# PCB_3U_DDS.net
KiCad netlist of a schematic drawn in Altium Designer
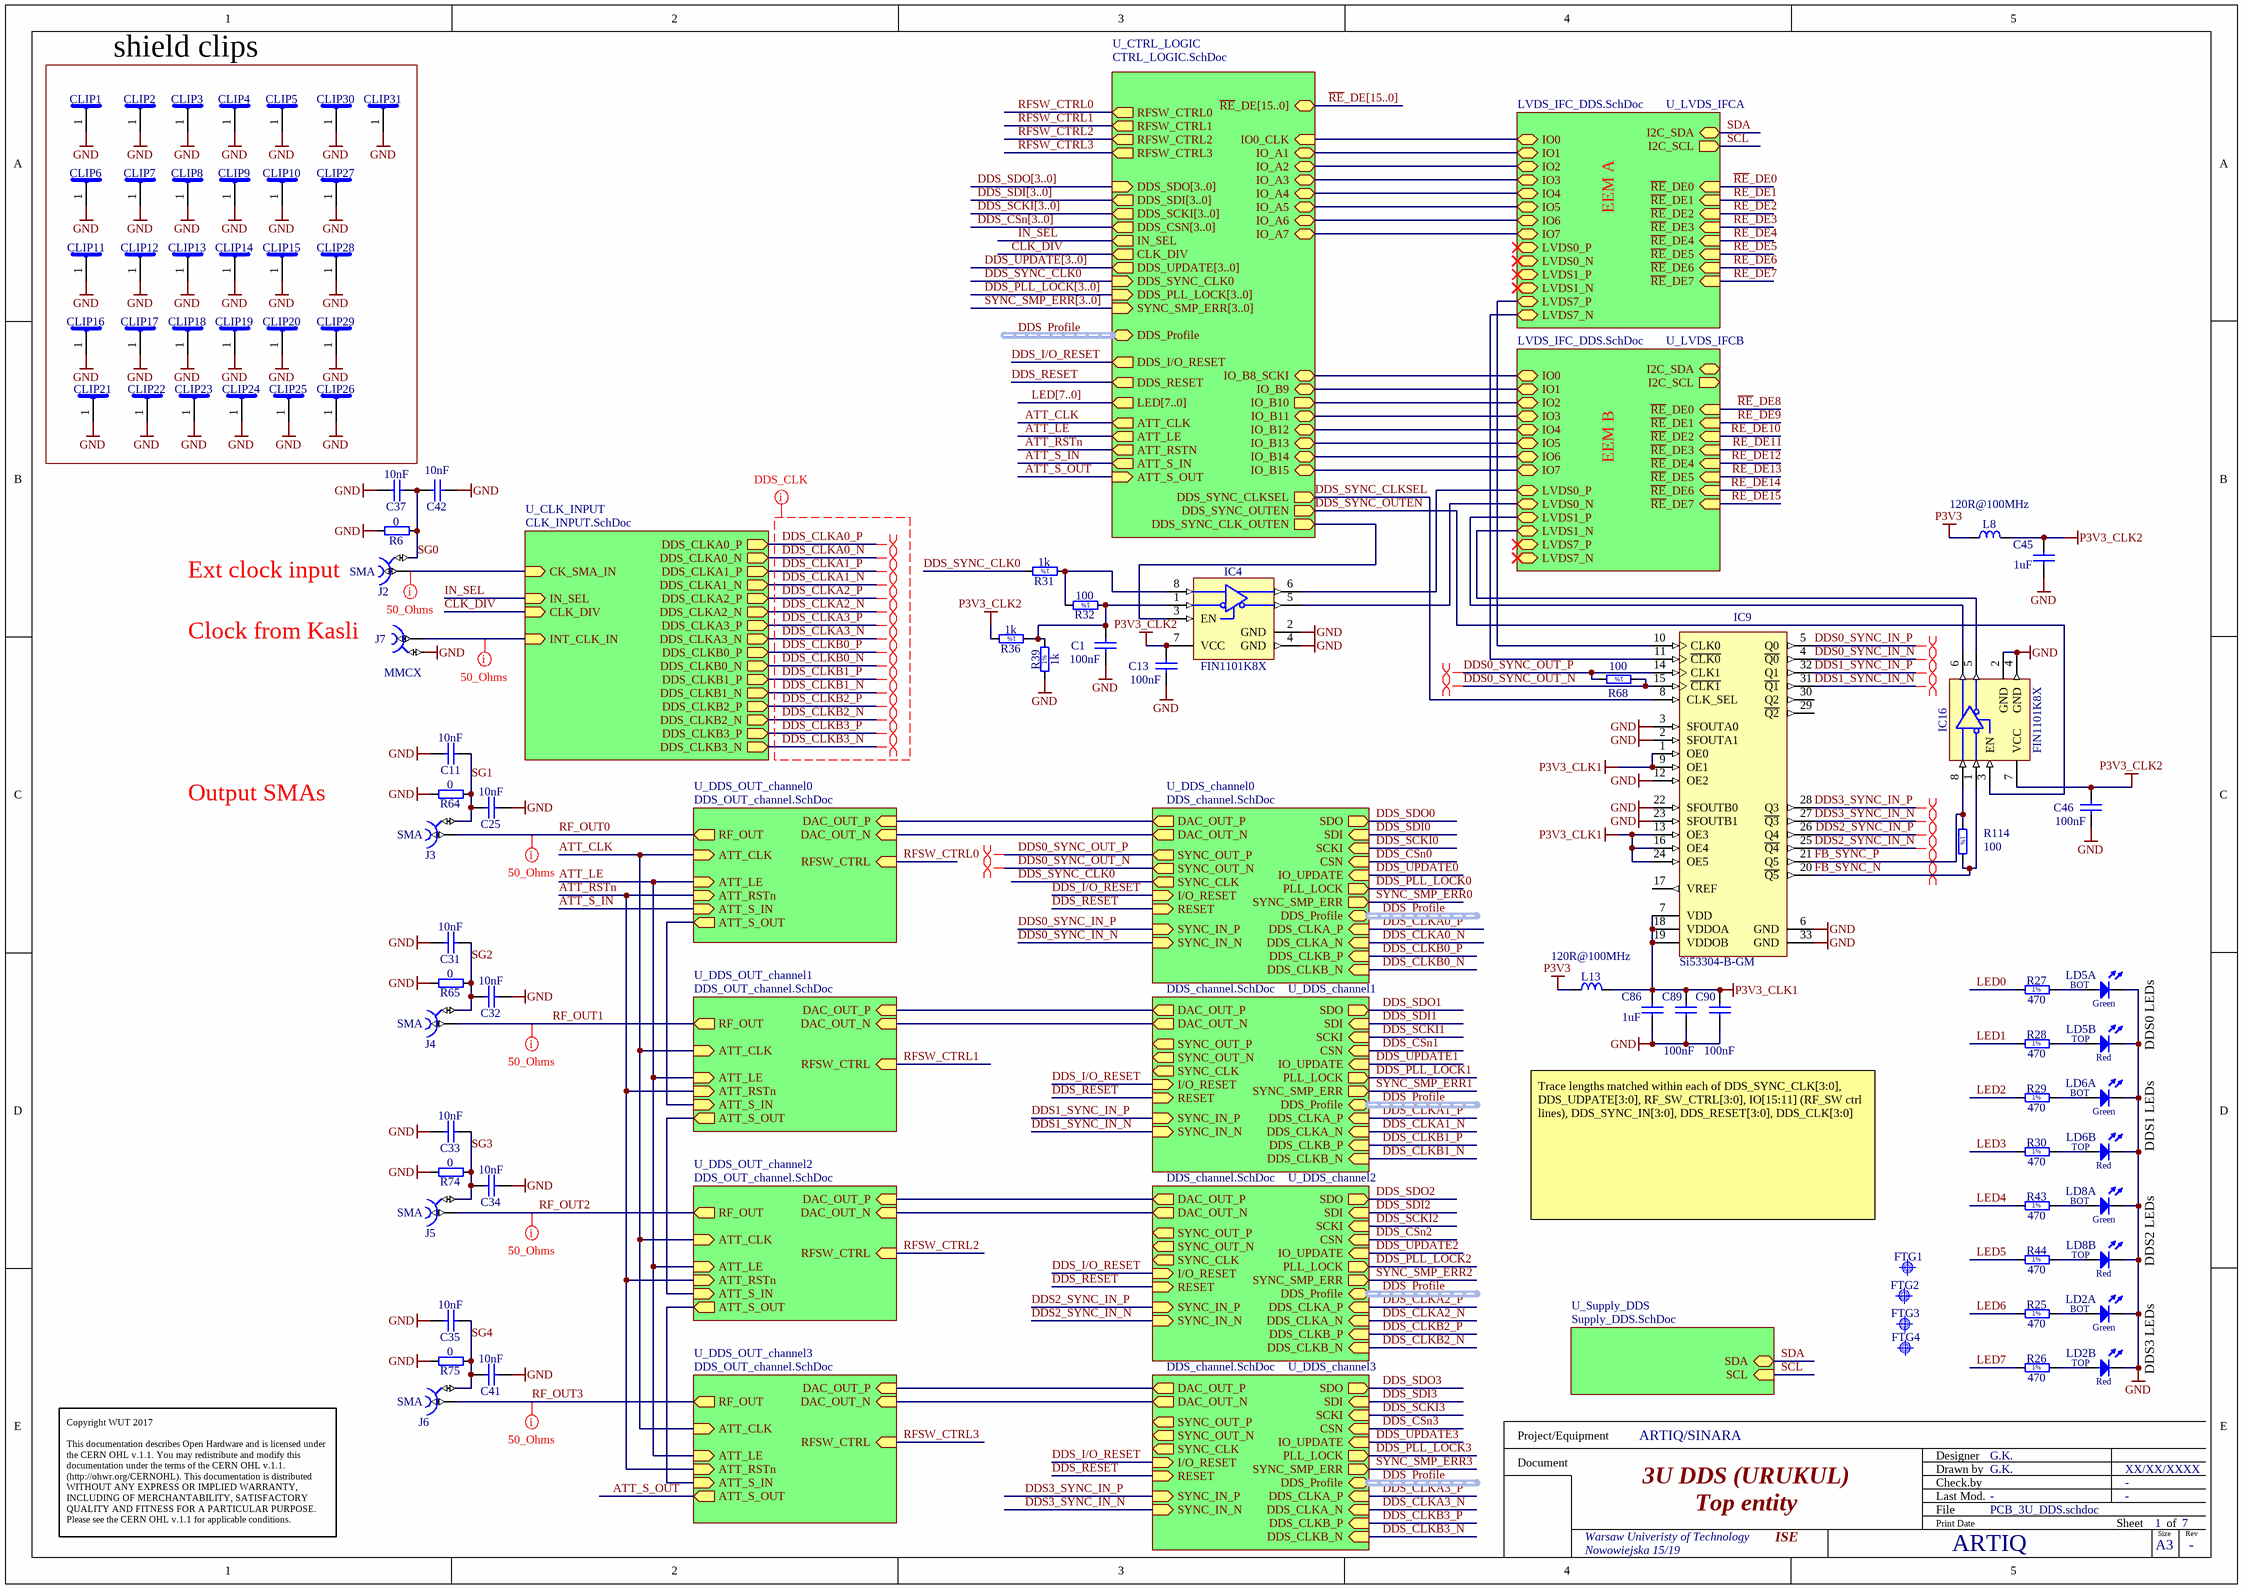
[diagram p0: PCB_3U_DDS.schdoc]

(export (version "E")
  (design (tool "Eeschema 10.0.6"))
  (components
    (comp (ref "C1")
      (value "100nF")
      (footprint "CAPC1005X55N")
      (description "Non-polarised capacitor")
      (fields
        (field (name "PART NUMBER") "CC0402_100NF_16V_10%_X5R")
        (field (name "VOLTAGE") "16V")
        (field (name "AUTHOR") "CERN DEM JLC")
      )
      (libsource (lib "Capacitors") (part "Capacitor - non polarized"))
    )
    (comp (ref "C11")
      (value "10nF")
      (footprint "CAPC1005X55N")
      (description "Non-polarised capacitor")
      (fields
        (field (name "PART NUMBER") "CC0402_10NF_16V_10%_X7R")
        (field (name "VOLTAGE") "16V")
        (field (name "AUTHOR") "CERN DEM JLC")
      )
      (libsource (lib "Capacitors") (part "Capacitor - non polarized"))
    )
    (comp (ref "C13")
      (value "100nF")
      (footprint "CAPC1005X55N")
      (description "Non-polarised capacitor")
      (fields
        (field (name "PART NUMBER") "CC0402_100NF_16V_10%_X5R")
        (field (name "VOLTAGE") "16V")
        (field (name "AUTHOR") "CERN DEM JLC")
      )
      (libsource (lib "Capacitors") (part "Capacitor - non polarized"))
    )
    (comp (ref "C25")
      (value "10nF")
      (footprint "CAPC1005X55N")
      (description "Non-polarised capacitor")
      (fields
        (field (name "PART NUMBER") "CC0402_10NF_16V_10%_X7R")
        (field (name "VOLTAGE") "16V")
        (field (name "AUTHOR") "CERN DEM JLC")
      )
      (libsource (lib "Capacitors") (part "Capacitor - non polarized"))
    )
    (comp (ref "C31")
      (value "10nF")
      (footprint "CAPC1005X55N")
      (description "Non-polarised capacitor")
      (fields
        (field (name "PART NUMBER") "CC0402_10NF_16V_10%_X7R")
        (field (name "VOLTAGE") "16V")
        (field (name "AUTHOR") "CERN DEM JLC")
      )
      (libsource (lib "Capacitors") (part "Capacitor - non polarized"))
    )
    (comp (ref "C32")
      (value "10nF")
      (footprint "CAPC1005X55N")
      (description "Non-polarised capacitor")
      (fields
        (field (name "PART NUMBER") "CC0402_10NF_16V_10%_X7R")
        (field (name "VOLTAGE") "16V")
        (field (name "AUTHOR") "CERN DEM JLC")
      )
      (libsource (lib "Capacitors") (part "Capacitor - non polarized"))
    )
    (comp (ref "C33")
      (value "10nF")
      (footprint "CAPC1005X55N")
      (description "Non-polarised capacitor")
      (fields
        (field (name "PART NUMBER") "CC0402_10NF_16V_10%_X7R")
        (field (name "VOLTAGE") "16V")
        (field (name "AUTHOR") "CERN DEM JLC")
      )
      (libsource (lib "Capacitors") (part "Capacitor - non polarized"))
    )
    (comp (ref "C34")
      (value "10nF")
      (footprint "CAPC1005X55N")
      (description "Non-polarised capacitor")
      (fields
        (field (name "PART NUMBER") "CC0402_10NF_16V_10%_X7R")
        (field (name "VOLTAGE") "16V")
        (field (name "AUTHOR") "CERN DEM JLC")
      )
      (libsource (lib "Capacitors") (part "Capacitor - non polarized"))
    )
    (comp (ref "C35")
      (value "10nF")
      (footprint "CAPC1005X55N")
      (description "Non-polarised capacitor")
      (fields
        (field (name "PART NUMBER") "CC0402_10NF_16V_10%_X7R")
        (field (name "VOLTAGE") "16V")
        (field (name "AUTHOR") "CERN DEM JLC")
      )
      (libsource (lib "Capacitors") (part "Capacitor - non polarized"))
    )
    (comp (ref "C37")
      (value "10nF")
      (footprint "CAPC1005X55N")
      (description "Non-polarised capacitor")
      (fields
        (field (name "PART NUMBER") "CC0402_10NF_16V_10%_X7R")
        (field (name "VOLTAGE") "16V")
        (field (name "AUTHOR") "CERN DEM JLC")
      )
      (libsource (lib "Capacitors") (part "Capacitor - non polarized"))
    )
    (comp (ref "C41")
      (value "10nF")
      (footprint "CAPC1005X55N")
      (description "Non-polarised capacitor")
      (fields
        (field (name "PART NUMBER") "CC0402_10NF_16V_10%_X7R")
        (field (name "VOLTAGE") "16V")
        (field (name "AUTHOR") "CERN DEM JLC")
      )
      (libsource (lib "Capacitors") (part "Capacitor - non polarized"))
    )
    (comp (ref "C42")
      (value "10nF")
      (footprint "CAPC1005X55N")
      (description "Non-polarised capacitor")
      (fields
        (field (name "PART NUMBER") "CC0402_10NF_16V_10%_X7R")
        (field (name "VOLTAGE") "16V")
        (field (name "AUTHOR") "CERN DEM JLC")
      )
      (libsource (lib "Capacitors") (part "Capacitor - non polarized"))
    )
    (comp (ref "C45")
      (value "1uF")
      (footprint "CAPC1005X55N")
      (description "Non-polarised capacitor")
      (fields
        (field (name "PART NUMBER") "CC0402_1UF_16V_10%_X5R")
        (field (name "VOLTAGE") "16V")
        (field (name "AUTHOR") "CERN DEM JLC")
      )
      (libsource (lib "Capacitors") (part "Capacitor - non polarized"))
    )
    (comp (ref "C46")
      (value "100nF")
      (footprint "CAPC1005X55N")
      (description "Non-polarised capacitor")
      (fields
        (field (name "PART NUMBER") "CC0402_100NF_16V_10%_X5R")
        (field (name "VOLTAGE") "16V")
        (field (name "AUTHOR") "CERN DEM JLC")
      )
      (libsource (lib "Capacitors") (part "Capacitor - non polarized"))
    )
    (comp (ref "C86")
      (value "1uF")
      (footprint "CAPC1005X55N")
      (description "Non-polarised capacitor")
      (fields
        (field (name "PART NUMBER") "CC0402_1UF_16V_10%_X5R")
        (field (name "VOLTAGE") "16V")
        (field (name "AUTHOR") "CERN DEM JLC")
      )
      (libsource (lib "Capacitors") (part "Capacitor - non polarized"))
    )
    (comp (ref "C89")
      (value "100nF")
      (footprint "CAPC1005X55N")
      (description "Non-polarised capacitor")
      (fields
        (field (name "PART NUMBER") "CC0402_100NF_16V_10%_X5R")
        (field (name "VOLTAGE") "16V")
        (field (name "AUTHOR") "CERN DEM JLC")
      )
      (libsource (lib "Capacitors") (part "Capacitor - non polarized"))
    )
    (comp (ref "C90")
      (value "100nF")
      (footprint "CAPC1005X55N")
      (description "Non-polarised capacitor")
      (fields
        (field (name "PART NUMBER") "CC0402_100NF_16V_10%_X5R")
        (field (name "VOLTAGE") "16V")
        (field (name "AUTHOR") "CERN DEM JLC")
      )
      (libsource (lib "Capacitors") (part "Capacitor - non polarized"))
    )
    (comp (ref "CLIP1")
      (value "S1411-46R")
      (footprint "CLIP_HOLLAND-SHIELDING_LC")
      (description "Surface Mount Clip for PCB Screening Covers")
      (fields (field (name "MANUFACTURER") "HARWIN") (field (name "AUTHOR") "CERN DEM JLC"))
      (libsource (lib "LIBRARY_SCH") (part "SHIELD_CLIP"))
    )
    (comp (ref "CLIP2")
      (value "S1411-46R")
      (footprint "CLIP_HOLLAND-SHIELDING_LC")
      (description "Surface Mount Clip for PCB Screening Covers")
      (fields (field (name "MANUFACTURER") "HARWIN") (field (name "AUTHOR") "CERN DEM JLC"))
      (libsource (lib "LIBRARY_SCH") (part "SHIELD_CLIP"))
    )
    (comp (ref "CLIP3")
      (value "S1411-46R")
      (footprint "CLIP_HOLLAND-SHIELDING_LC")
      (description "Surface Mount Clip for PCB Screening Covers")
      (fields (field (name "MANUFACTURER") "HARWIN") (field (name "AUTHOR") "CERN DEM JLC"))
      (libsource (lib "LIBRARY_SCH") (part "SHIELD_CLIP"))
    )
    (comp (ref "CLIP4")
      (value "S1411-46R")
      (footprint "CLIP_HOLLAND-SHIELDING_LC")
      (description "Surface Mount Clip for PCB Screening Covers")
      (fields (field (name "MANUFACTURER") "HARWIN") (field (name "AUTHOR") "CERN DEM JLC"))
      (libsource (lib "LIBRARY_SCH") (part "SHIELD_CLIP"))
    )
    (comp (ref "CLIP5")
      (value "S1411-46R")
      (footprint "CLIP_HOLLAND-SHIELDING_LC")
      (description "Surface Mount Clip for PCB Screening Covers")
      (fields (field (name "MANUFACTURER") "HARWIN") (field (name "AUTHOR") "CERN DEM JLC"))
      (libsource (lib "LIBRARY_SCH") (part "SHIELD_CLIP"))
    )
    (comp (ref "CLIP6")
      (value "S1411-46R")
      (footprint "CLIP_HOLLAND-SHIELDING_LC")
      (description "Surface Mount Clip for PCB Screening Covers")
      (fields (field (name "MANUFACTURER") "HARWIN") (field (name "AUTHOR") "CERN DEM JLC"))
      (libsource (lib "LIBRARY_SCH") (part "SHIELD_CLIP"))
    )
    (comp (ref "CLIP7")
      (value "S1411-46R")
      (footprint "CLIP_HOLLAND-SHIELDING_LC")
      (description "Surface Mount Clip for PCB Screening Covers")
      (fields (field (name "MANUFACTURER") "HARWIN") (field (name "AUTHOR") "CERN DEM JLC"))
      (libsource (lib "LIBRARY_SCH") (part "SHIELD_CLIP"))
    )
    (comp (ref "CLIP8")
      (value "S1411-46R")
      (footprint "CLIP_HOLLAND-SHIELDING_LC")
      (description "Surface Mount Clip for PCB Screening Covers")
      (fields (field (name "MANUFACTURER") "HARWIN") (field (name "AUTHOR") "CERN DEM JLC"))
      (libsource (lib "LIBRARY_SCH") (part "SHIELD_CLIP"))
    )
    (comp (ref "CLIP9")
      (value "S1411-46R")
      (footprint "CLIP_HOLLAND-SHIELDING_LC")
      (description "Surface Mount Clip for PCB Screening Covers")
      (fields (field (name "MANUFACTURER") "HARWIN") (field (name "AUTHOR") "CERN DEM JLC"))
      (libsource (lib "LIBRARY_SCH") (part "SHIELD_CLIP"))
    )
    (comp (ref "CLIP10")
      (value "S1411-46R")
      (footprint "CLIP_HOLLAND-SHIELDING_LC")
      (description "Surface Mount Clip for PCB Screening Covers")
      (fields (field (name "MANUFACTURER") "HARWIN") (field (name "AUTHOR") "CERN DEM JLC"))
      (libsource (lib "LIBRARY_SCH") (part "SHIELD_CLIP"))
    )
    (comp (ref "CLIP11")
      (value "S1411-46R")
      (footprint "CLIP_HOLLAND-SHIELDING_LC")
      (description "Surface Mount Clip for PCB Screening Covers")
      (fields (field (name "MANUFACTURER") "HARWIN") (field (name "AUTHOR") "CERN DEM JLC"))
      (libsource (lib "LIBRARY_SCH") (part "SHIELD_CLIP"))
    )
    (comp (ref "CLIP12")
      (value "S1411-46R")
      (footprint "CLIP_HOLLAND-SHIELDING_LC")
      (description "Surface Mount Clip for PCB Screening Covers")
      (fields (field (name "MANUFACTURER") "HARWIN") (field (name "AUTHOR") "CERN DEM JLC"))
      (libsource (lib "LIBRARY_SCH") (part "SHIELD_CLIP"))
    )
    (comp (ref "CLIP13")
      (value "S1411-46R")
      (footprint "CLIP_HOLLAND-SHIELDING_LC")
      (description "Surface Mount Clip for PCB Screening Covers")
      (fields (field (name "MANUFACTURER") "HARWIN") (field (name "AUTHOR") "CERN DEM JLC"))
      (libsource (lib "LIBRARY_SCH") (part "SHIELD_CLIP"))
    )
    (comp (ref "CLIP14")
      (value "S1411-46R")
      (footprint "CLIP_HOLLAND-SHIELDING_LC")
      (description "Surface Mount Clip for PCB Screening Covers")
      (fields (field (name "MANUFACTURER") "HARWIN") (field (name "AUTHOR") "CERN DEM JLC"))
      (libsource (lib "LIBRARY_SCH") (part "SHIELD_CLIP"))
    )
    (comp (ref "CLIP15")
      (value "S1411-46R")
      (footprint "CLIP_HOLLAND-SHIELDING_LC")
      (description "Surface Mount Clip for PCB Screening Covers")
      (fields (field (name "MANUFACTURER") "HARWIN") (field (name "AUTHOR") "CERN DEM JLC"))
      (libsource (lib "LIBRARY_SCH") (part "SHIELD_CLIP"))
    )
    (comp (ref "CLIP16")
      (value "S1411-46R")
      (footprint "CLIP_HOLLAND-SHIELDING_LC")
      (description "Surface Mount Clip for PCB Screening Covers")
      (fields (field (name "MANUFACTURER") "HARWIN") (field (name "AUTHOR") "CERN DEM JLC"))
      (libsource (lib "LIBRARY_SCH") (part "SHIELD_CLIP"))
    )
    (comp (ref "CLIP17")
      (value "S1411-46R")
      (footprint "CLIP_HOLLAND-SHIELDING_LC")
      (description "Surface Mount Clip for PCB Screening Covers")
      (fields (field (name "MANUFACTURER") "HARWIN") (field (name "AUTHOR") "CERN DEM JLC"))
      (libsource (lib "LIBRARY_SCH") (part "SHIELD_CLIP"))
    )
    (comp (ref "CLIP18")
      (value "S1411-46R")
      (footprint "CLIP_HOLLAND-SHIELDING_LC")
      (description "Surface Mount Clip for PCB Screening Covers")
      (fields (field (name "MANUFACTURER") "HARWIN") (field (name "AUTHOR") "CERN DEM JLC"))
      (libsource (lib "LIBRARY_SCH") (part "SHIELD_CLIP"))
    )
    (comp (ref "CLIP19")
      (value "S1411-46R")
      (footprint "CLIP_HOLLAND-SHIELDING_LC")
      (description "Surface Mount Clip for PCB Screening Covers")
      (fields (field (name "MANUFACTURER") "HARWIN") (field (name "AUTHOR") "CERN DEM JLC"))
      (libsource (lib "LIBRARY_SCH") (part "SHIELD_CLIP"))
    )
    (comp (ref "CLIP20")
      (value "S1411-46R")
      (footprint "CLIP_HOLLAND-SHIELDING_LC")
      (description "Surface Mount Clip for PCB Screening Covers")
      (fields (field (name "MANUFACTURER") "HARWIN") (field (name "AUTHOR") "CERN DEM JLC"))
      (libsource (lib "LIBRARY_SCH") (part "SHIELD_CLIP"))
    )
    (comp (ref "CLIP21")
      (value "S1411-46R")
      (footprint "CLIP_HOLLAND-SHIELDING_LC")
      (description "Surface Mount Clip for PCB Screening Covers")
      (fields (field (name "MANUFACTURER") "HARWIN") (field (name "AUTHOR") "CERN DEM JLC"))
      (libsource (lib "LIBRARY_SCH") (part "SHIELD_CLIP"))
    )
    (comp (ref "CLIP22")
      (value "S1411-46R")
      (footprint "CLIP_HOLLAND-SHIELDING_LC")
      (description "Surface Mount Clip for PCB Screening Covers")
      (fields (field (name "MANUFACTURER") "HARWIN") (field (name "AUTHOR") "CERN DEM JLC"))
      (libsource (lib "LIBRARY_SCH") (part "SHIELD_CLIP"))
    )
    (comp (ref "CLIP23")
      (value "S1411-46R")
      (footprint "CLIP_HOLLAND-SHIELDING_LC")
      (description "Surface Mount Clip for PCB Screening Covers")
      (fields (field (name "MANUFACTURER") "HARWIN") (field (name "AUTHOR") "CERN DEM JLC"))
      (libsource (lib "LIBRARY_SCH") (part "SHIELD_CLIP"))
    )
    (comp (ref "CLIP24")
      (value "S1411-46R")
      (footprint "CLIP_HOLLAND-SHIELDING_LC")
      (description "Surface Mount Clip for PCB Screening Covers")
      (fields (field (name "MANUFACTURER") "HARWIN") (field (name "AUTHOR") "CERN DEM JLC"))
      (libsource (lib "LIBRARY_SCH") (part "SHIELD_CLIP"))
    )
    (comp (ref "CLIP25")
      (value "S1411-46R")
      (footprint "CLIP_HOLLAND-SHIELDING_LC")
      (description "Surface Mount Clip for PCB Screening Covers")
      (fields (field (name "MANUFACTURER") "HARWIN") (field (name "AUTHOR") "CERN DEM JLC"))
      (libsource (lib "LIBRARY_SCH") (part "SHIELD_CLIP"))
    )
    (comp (ref "CLIP26")
      (value "S1411-46R")
      (footprint "CLIP_HOLLAND-SHIELDING_LC")
      (description "Surface Mount Clip for PCB Screening Covers")
      (fields (field (name "MANUFACTURER") "HARWIN") (field (name "AUTHOR") "CERN DEM JLC"))
      (libsource (lib "LIBRARY_SCH") (part "SHIELD_CLIP"))
    )
    (comp (ref "CLIP27")
      (value "S1411-46R")
      (footprint "CLIP_HOLLAND-SHIELDING_LC")
      (description "Surface Mount Clip for PCB Screening Covers")
      (fields (field (name "MANUFACTURER") "HARWIN") (field (name "AUTHOR") "CERN DEM JLC"))
      (libsource (lib "LIBRARY_SCH") (part "SHIELD_CLIP"))
    )
    (comp (ref "CLIP28")
      (value "S1411-46R")
      (footprint "CLIP_HOLLAND-SHIELDING_LC")
      (description "Surface Mount Clip for PCB Screening Covers")
      (fields (field (name "MANUFACTURER") "HARWIN") (field (name "AUTHOR") "CERN DEM JLC"))
      (libsource (lib "LIBRARY_SCH") (part "SHIELD_CLIP"))
    )
    (comp (ref "CLIP29")
      (value "S1411-46R")
      (footprint "CLIP_HOLLAND-SHIELDING_LC")
      (description "Surface Mount Clip for PCB Screening Covers")
      (fields (field (name "MANUFACTURER") "HARWIN") (field (name "AUTHOR") "CERN DEM JLC"))
      (libsource (lib "LIBRARY_SCH") (part "SHIELD_CLIP"))
    )
    (comp (ref "CLIP30")
      (value "S1411-46R")
      (footprint "CLIP_HOLLAND-SHIELDING_LC")
      (description "Surface Mount Clip for PCB Screening Covers")
      (fields (field (name "MANUFACTURER") "HARWIN") (field (name "AUTHOR") "CERN DEM JLC"))
      (libsource (lib "LIBRARY_SCH") (part "SHIELD_CLIP"))
    )
    (comp (ref "CLIP31")
      (value "S1411-46R")
      (footprint "CLIP_HOLLAND-SHIELDING_LC")
      (description "Surface Mount Clip for PCB Screening Covers")
      (fields (field (name "MANUFACTURER") "HARWIN") (field (name "AUTHOR") "CERN DEM JLC"))
      (libsource (lib "LIBRARY_SCH") (part "SHIELD_CLIP"))
    )
    (comp (ref "FTG1")
      (value "Use only in PCB")
      (footprint "FIDUCIAL_TOP_C100-200")
      (description "Fiducial Target")
      (fields (field (name "PART NUMBER") "FIDUCIAL_TARGET_C100-200") (field (name "AUTHOR") "CERN DEM JLC"))
      (libsource (lib "Eletro-mechanical") (part "Fiducial Target"))
    )
    (comp (ref "FTG2")
      (value "Use only in PCB")
      (footprint "FIDUCIAL_TOP_S100-200")
      (description "Fiducial Target")
      (fields (field (name "PART NUMBER") "FIDUCIAL_TARGET_S100-200") (field (name "AUTHOR") "CERN DEM JLC"))
      (libsource (lib "Eletro-mechanical") (part "Fiducial Target"))
    )
    (comp (ref "FTG3")
      (value "Use only in PCB")
      (footprint "FIDUCIAL_TOP_S200-400")
      (description "Fiducial Target")
      (fields (field (name "PART NUMBER") "FIDUCIAL_TARGET_S200-400") (field (name "AUTHOR") "CERN DEM JLC"))
      (libsource (lib "Eletro-mechanical") (part "Fiducial Target"))
    )
    (comp (ref "FTG4")
      (value "Use only in PCB")
      (footprint "FIDUCIAL_TOP_S100-200")
      (description "Fiducial Target")
      (fields (field (name "PART NUMBER") "FIDUCIAL_TARGET_S100-200") (field (name "AUTHOR") "CERN DEM JLC"))
      (libsource (lib "Eletro-mechanical") (part "Fiducial Target"))
    )
    (comp (ref "IC4")
      (value "FIN1101K8X")
      (footprint "SOP50P310X90-8N")
      (description "LVDS Single Port High Speed Repeater")
      (fields (field (name "MANUFACTURER") "FAIRCHILD SEMICONDUCTOR") (field (name "AUTHOR") "CERN DEM JLC"))
      (libsource (lib "ICs And Semiconductors") (part "FIN1101K8X"))
    )
    (comp (ref "IC9")
      (value "Si53304-B-GM")
      (footprint "SLAB-QFN-32-2150x2150TP_M")
      (fields (field (name "MANUFACTURER") "Silicon Labs"))
      (libsource (lib "Altium Content Vault") (part "SLAB-Si533X4-QFN-32-33"))
    )
    (comp (ref "IC16")
      (value "FIN1101K8X")
      (footprint "SOP50P310X90-8N")
      (description "LVDS Single Port High Speed Repeater")
      (fields (field (name "MANUFACTURER") "FAIRCHILD SEMICONDUCTOR") (field (name "AUTHOR") "CERN DEM JLC"))
      (libsource (lib "") (part "FIN1101K8X_1"))
    )
    (comp (ref "J2")
      (value "SMA")
      (footprint "RF249BT0050GHDW")
      (description "50 Ohm Through Hole SMA Right Angle PCB Jack")
      (fields
        (field (name "PART NUMBER") "AdamTech_RF249BT0050GHDW")
        (field (name "MANUFACTURER") "AdamTech")
        (field (name "AUTHOR") "GK")
      )
      (libsource (lib "LIBRARY_SCH") (part "CON_SMA_RF249BT0050GHDW"))
    )
    (comp (ref "J3")
      (value "SMA")
      (footprint "RF249BT0050GHDW")
      (description "50 Ohm Through Hole SMA Right Angle PCB Jack")
      (fields
        (field (name "PART NUMBER") "AdamTech_RF249BT0050GHDW")
        (field (name "MANUFACTURER") "AdamTech")
        (field (name "AUTHOR") "GK")
      )
      (libsource (lib "LIBRARY_SCH") (part "CON_SMA_RF249BT0050GHDW"))
    )
    (comp (ref "J4")
      (value "SMA")
      (footprint "RF249BT0050GHDW")
      (description "50 Ohm Through Hole SMA Right Angle PCB Jack")
      (fields
        (field (name "PART NUMBER") "AdamTech_RF249BT0050GHDW")
        (field (name "MANUFACTURER") "AdamTech")
        (field (name "AUTHOR") "GK")
      )
      (libsource (lib "LIBRARY_SCH") (part "CON_SMA_RF249BT0050GHDW"))
    )
    (comp (ref "J5")
      (value "SMA")
      (footprint "RF249BT0050GHDW")
      (description "50 Ohm Through Hole SMA Right Angle PCB Jack")
      (fields
        (field (name "PART NUMBER") "AdamTech_RF249BT0050GHDW")
        (field (name "MANUFACTURER") "AdamTech")
        (field (name "AUTHOR") "GK")
      )
      (libsource (lib "LIBRARY_SCH") (part "CON_SMA_RF249BT0050GHDW"))
    )
    (comp (ref "J6")
      (value "SMA")
      (footprint "RF249BT0050GHDW")
      (description "50 Ohm Through Hole SMA Right Angle PCB Jack")
      (fields
        (field (name "PART NUMBER") "AdamTech_RF249BT0050GHDW")
        (field (name "MANUFACTURER") "AdamTech")
        (field (name "AUTHOR") "GK")
      )
      (libsource (lib "LIBRARY_SCH") (part "CON_SMA_RF249BT0050GHDW"))
    )
    (comp (ref "J7")
      (value "MMCX")
      (footprint "SAMTEC_MMCX-J-P-H-ST-TH1")
      (fields
        (field (name "PART NUMBER") "SAMTEC_MMCX-J-P-H-ST-TH1")
        (field (name "MANUFACTURER") "SAMTEC")
        (field (name "MANUFACTURER PART NUMBER") "MMCX-J-P-H-ST-TH1")
        (field (name "AUTHOR") "CERN DEM JLC")
      )
      (libsource (lib "Connectors") (part "Coax_1Female_1Shield"))
    )
    (comp (ref "L8")
      (value "120R@100MHz")
      (footprint "INDC1608X95N")
      (description "Inductor")
      (fields
        (field (name "PART NUMBER") "IND0603_MURATA_BLM18PG121SN1D")
        (field (name "POWER") "2A")
        (field (name "AUTHOR") "CERN DEM BC")
      )
      (libsource (lib "Inductors & Transformers") (part "Inductor"))
    )
    (comp (ref "L13")
      (value "120R@100MHz")
      (footprint "INDC1608X95N")
      (description "Inductor")
      (fields
        (field (name "PART NUMBER") "IND0603_MURATA_BLM18PG121SN1D")
        (field (name "POWER") "2A")
        (field (name "AUTHOR") "CERN DEM BC")
      )
      (libsource (lib "Inductors & Transformers") (part "Inductor"))
    )
    (comp (ref "LD2")
      (value "Red/Green")
      (footprint "LED_DIALIGHT_553-0112-200F")
      (description "2x LED  Botom Green, Top Red")
      (fields
        (field (name "PART NUMBER") "LED_DIALIGHT_553-0112-200F")
        (field (name "MANUFACTURER") "DIALIGHT")
        (field (name "AUTHOR") "CERN DEM JMW")
      )
      (libsource (lib "ICs And Semiconductors") (part "LED x2 G-1C2A-BOT_R-3C4A-TOP"))
    )
    (comp (ref "LD5")
      (value "Red/Green")
      (footprint "LED_DIALIGHT_553-0112-200F")
      (description "2x LED  Botom Green, Top Red")
      (fields
        (field (name "PART NUMBER") "LED_DIALIGHT_553-0112-200F")
        (field (name "MANUFACTURER") "DIALIGHT")
        (field (name "AUTHOR") "CERN DEM JMW")
      )
      (libsource (lib "ICs And Semiconductors") (part "LED x2 G-1C2A-BOT_R-3C4A-TOP"))
    )
    (comp (ref "LD6")
      (value "Red/Green")
      (footprint "LED_DIALIGHT_553-0112-200F")
      (description "2x LED  Botom Green, Top Red")
      (fields
        (field (name "PART NUMBER") "LED_DIALIGHT_553-0112-200F")
        (field (name "MANUFACTURER") "DIALIGHT")
        (field (name "AUTHOR") "CERN DEM JMW")
      )
      (libsource (lib "ICs And Semiconductors") (part "LED x2 G-1C2A-BOT_R-3C4A-TOP"))
    )
    (comp (ref "LD8")
      (value "Red/Green")
      (footprint "LED_DIALIGHT_553-0112-200F")
      (description "2x LED  Botom Green, Top Red")
      (fields
        (field (name "PART NUMBER") "LED_DIALIGHT_553-0112-200F")
        (field (name "MANUFACTURER") "DIALIGHT")
        (field (name "AUTHOR") "CERN DEM JMW")
      )
      (libsource (lib "ICs And Semiconductors") (part "LED x2 G-1C2A-BOT_R-3C4A-TOP"))
    )
    (comp (ref "R6")
      (value "0")
      (footprint "RESC1005X40N")
      (description "Resistor")
      (fields
        (field (name "PART NUMBER") "R0402_0R_JUMPER")
        (field (name "MANUFACTURER") "GENERIC")
        (field (name "AUTHOR") "CERN DEM JLC")
      )
      (libsource (lib "Resistors") (part "Resistor"))
    )
    (comp (ref "R25")
      (value "470")
      (footprint "RESC1005X40N")
      (description "Resistor - 1%")
      (fields
        (field (name "PART NUMBER") "R0402_470R_1%_0.0625W_100PPM")
        (field (name "POWER") "0.0625W")
        (field (name "AUTHOR") "CERN DEM JLC")
      )
      (libsource (lib "Resistors") (part "Resistor - 1%"))
    )
    (comp (ref "R26")
      (value "470")
      (footprint "RESC1005X40N")
      (description "Resistor - 1%")
      (fields
        (field (name "PART NUMBER") "R0402_470R_1%_0.0625W_100PPM")
        (field (name "POWER") "0.0625W")
        (field (name "AUTHOR") "CERN DEM JLC")
      )
      (libsource (lib "Resistors") (part "Resistor - 1%"))
    )
    (comp (ref "R27")
      (value "470")
      (footprint "RESC1005X40N")
      (description "Resistor - 1%")
      (fields
        (field (name "PART NUMBER") "R0402_470R_1%_0.0625W_100PPM")
        (field (name "POWER") "0.0625W")
        (field (name "AUTHOR") "CERN DEM JLC")
      )
      (libsource (lib "Resistors") (part "Resistor - 1%"))
    )
    (comp (ref "R28")
      (value "470")
      (footprint "RESC1005X40N")
      (description "Resistor - 1%")
      (fields
        (field (name "PART NUMBER") "R0402_470R_1%_0.0625W_100PPM")
        (field (name "POWER") "0.0625W")
        (field (name "AUTHOR") "CERN DEM JLC")
      )
      (libsource (lib "Resistors") (part "Resistor - 1%"))
    )
    (comp (ref "R29")
      (value "470")
      (footprint "RESC1005X40N")
      (description "Resistor - 1%")
      (fields
        (field (name "PART NUMBER") "R0402_470R_1%_0.0625W_100PPM")
        (field (name "POWER") "0.0625W")
        (field (name "AUTHOR") "CERN DEM JLC")
      )
      (libsource (lib "Resistors") (part "Resistor - 1%"))
    )
    (comp (ref "R30")
      (value "470")
      (footprint "RESC1005X40N")
      (description "Resistor - 1%")
      (fields
        (field (name "PART NUMBER") "R0402_470R_1%_0.0625W_100PPM")
        (field (name "POWER") "0.0625W")
        (field (name "AUTHOR") "CERN DEM JLC")
      )
      (libsource (lib "Resistors") (part "Resistor - 1%"))
    )
    (comp (ref "R31")
      (value "1k")
      (footprint "RESC1005X40N")
      (description "Resistor - 1%")
      (fields
        (field (name "PART NUMBER") "R0402_1K_1%_0.0625W_100PPM")
        (field (name "POWER") "0.0625W")
        (field (name "AUTHOR") "CERN DEM JLC")
      )
      (libsource (lib "Resistors") (part "Resistor - 1%"))
    )
    (comp (ref "R32")
      (value "100")
      (footprint "RESC1005X40N")
      (description "Resistor - 1%")
      (fields
        (field (name "PART NUMBER") "R0402_100R_1%_0.0625W_100PPM")
        (field (name "POWER") "0.0625W")
        (field (name "AUTHOR") "CERN DEM JLC")
      )
      (libsource (lib "Resistors") (part "Resistor - 1%"))
    )
    (comp (ref "R36")
      (value "1k")
      (footprint "RESC1005X40N")
      (description "Resistor - 1%")
      (fields
        (field (name "PART NUMBER") "R0402_1K_1%_0.0625W_100PPM")
        (field (name "POWER") "0.0625W")
        (field (name "AUTHOR") "CERN DEM JLC")
      )
      (libsource (lib "Resistors") (part "Resistor - 1%"))
    )
    (comp (ref "R39")
      (value "1k")
      (footprint "RESC1005X40N")
      (description "Resistor - 1%")
      (fields
        (field (name "PART NUMBER") "R0402_1K_1%_0.0625W_100PPM")
        (field (name "POWER") "0.0625W")
        (field (name "AUTHOR") "CERN DEM JLC")
      )
      (libsource (lib "Resistors") (part "Resistor - 1%"))
    )
    (comp (ref "R43")
      (value "470")
      (footprint "RESC1005X40N")
      (description "Resistor - 1%")
      (fields
        (field (name "PART NUMBER") "R0402_470R_1%_0.0625W_100PPM")
        (field (name "POWER") "0.0625W")
        (field (name "AUTHOR") "CERN DEM JLC")
      )
      (libsource (lib "Resistors") (part "Resistor - 1%"))
    )
    (comp (ref "R44")
      (value "470")
      (footprint "RESC1005X40N")
      (description "Resistor - 1%")
      (fields
        (field (name "PART NUMBER") "R0402_470R_1%_0.0625W_100PPM")
        (field (name "POWER") "0.0625W")
        (field (name "AUTHOR") "CERN DEM JLC")
      )
      (libsource (lib "Resistors") (part "Resistor - 1%"))
    )
    (comp (ref "R64")
      (value "0")
      (footprint "RESC1005X40N")
      (description "Resistor")
      (fields
        (field (name "PART NUMBER") "R0402_0R_JUMPER")
        (field (name "MANUFACTURER") "GENERIC")
        (field (name "AUTHOR") "CERN DEM JLC")
      )
      (libsource (lib "Resistors") (part "Resistor"))
    )
    (comp (ref "R65")
      (value "0")
      (footprint "RESC1005X40N")
      (description "Resistor")
      (fields
        (field (name "PART NUMBER") "R0402_0R_JUMPER")
        (field (name "MANUFACTURER") "GENERIC")
        (field (name "AUTHOR") "CERN DEM JLC")
      )
      (libsource (lib "Resistors") (part "Resistor"))
    )
    (comp (ref "R68")
      (value "100")
      (footprint "RESC1005X40N")
      (description "Resistor - 1%")
      (fields
        (field (name "PART NUMBER") "R0402_100R_1%_0.0625W_100PPM")
        (field (name "POWER") "0.0625W")
        (field (name "AUTHOR") "CERN DEM JLC")
      )
      (libsource (lib "Resistors") (part "Resistor - 1%"))
    )
    (comp (ref "R74")
      (value "0")
      (footprint "RESC1005X40N")
      (description "Resistor")
      (fields
        (field (name "PART NUMBER") "R0402_0R_JUMPER")
        (field (name "MANUFACTURER") "GENERIC")
        (field (name "AUTHOR") "CERN DEM JLC")
      )
      (libsource (lib "Resistors") (part "Resistor"))
    )
    (comp (ref "R75")
      (value "0")
      (footprint "RESC1005X40N")
      (description "Resistor")
      (fields
        (field (name "PART NUMBER") "R0402_0R_JUMPER")
        (field (name "MANUFACTURER") "GENERIC")
        (field (name "AUTHOR") "CERN DEM JLC")
      )
      (libsource (lib "Resistors") (part "Resistor"))
    )
    (comp (ref "R114")
      (value "100")
      (footprint "RESC1005X40N")
      (description "Resistor - 1%")
      (fields
        (field (name "PART NUMBER") "R0402_100R_1%_0.0625W_100PPM")
        (field (name "POWER") "0.0625W")
        (field (name "AUTHOR") "CERN DEM JLC")
      )
      (libsource (lib "Resistors") (part "Resistor - 1%"))
    )
  )
  (nets
    (net (code "10") (name "/CK_SMA_IN") (class "Default")
      (node (ref "J2") (pin "1") (pinfunction "1_1") (pintype "bidirectional"))
    )
    (net (code "20") (name "/DDS0_SYNC_IN_N") (class "Default")
      (node (ref "IC9") (pin "4") (pinfunction "~{Q0}_4") (pintype "output"))
    )
    (net (code "21") (name "/DDS0_SYNC_IN_P") (class "Default")
      (node (ref "IC9") (pin "5") (pinfunction "Q0_5") (pintype "output"))
    )
    (net (code "22") (name "/DDS0_SYNC_OUT_N") (class "Default")
      (node (ref "IC9") (pin "15") (pinfunction "~{CLK1}_15") (pintype "input"))
      (node (ref "R68") (pin "1") (pinfunction "1_1") (pintype "passive"))
    )
    (net (code "23") (name "/DDS0_SYNC_OUT_P") (class "Default")
      (node (ref "IC9") (pin "14") (pinfunction "CLK1_14") (pintype "input"))
      (node (ref "R68") (pin "2") (pinfunction "2_2") (pintype "passive"))
    )
    (net (code "24") (name "/DDS1_SYNC_IN_N") (class "Default")
      (node (ref "IC9") (pin "31") (pinfunction "~{Q1}_31") (pintype "output"))
    )
    (net (code "25") (name "/DDS1_SYNC_IN_P") (class "Default")
      (node (ref "IC9") (pin "32") (pinfunction "Q1_32") (pintype "output"))
    )
    (net (code "26") (name "/DDS2_SYNC_IN_N") (class "Default")
      (node (ref "IC9") (pin "25") (pinfunction "~{Q4}_25") (pintype "output"))
    )
    (net (code "27") (name "/DDS2_SYNC_IN_P") (class "Default")
      (node (ref "IC9") (pin "26") (pinfunction "Q4_26") (pintype "output"))
    )
    (net (code "28") (name "/DDS3_SYNC_IN_N") (class "Default")
      (node (ref "IC9") (pin "27") (pinfunction "~{Q3}_27") (pintype "output"))
    )
    (net (code "29") (name "/DDS3_SYNC_IN_P") (class "Default")
      (node (ref "IC9") (pin "28") (pinfunction "Q3_28") (pintype "output"))
    )
    (net (code "73") (name "/DDS_SYNC_CLK0") (class "Default")
      (node (ref "R31") (pin "2") (pinfunction "2_2") (pintype "passive"))
    )
    (net (code "74") (name "/DDS_SYNC_CLKSEL") (class "Default")
      (node (ref "IC9") (pin "8") (pinfunction "CLK_SEL_8") (pintype "input"))
    )
    (net (code "75") (name "/DDS_SYNC_CLK_OUTEN") (class "Default")
      (node (ref "IC4") (pin "3") (pinfunction "EN_3") (pintype "input"))
    )
    (net (code "76") (name "/DDS_SYNC_OUTEN") (class "Default")
      (node (ref "IC16") (pin "3") (pinfunction "EN_3") (pintype "input"))
    )
    (net (code "82") (name "/FB_SYNC_N") (class "Default")
      (node (ref "IC16") (pin "1") (pinfunction "RIN-_1") (pintype "input"))
      (node (ref "IC9") (pin "20") (pinfunction "~{Q5}_20") (pintype "output"))
      (node (ref "R114") (pin "2") (pinfunction "2_2") (pintype "passive"))
    )
    (net (code "83") (name "/FB_SYNC_P") (class "Default")
      (node (ref "IC16") (pin "8") (pinfunction "RIN+_8") (pintype "input"))
      (node (ref "IC9") (pin "21") (pinfunction "Q5_21") (pintype "output"))
      (node (ref "R114") (pin "1") (pinfunction "1_1") (pintype "passive"))
    )
    (net (code "86") (name "/INT_CLK_IN") (class "Default")
      (node (ref "J7") (pin "1") (pinfunction "1_1") (pintype "bidirectional"))
    )
    (net (code "104") (name "/LED0") (class "Default")
      (node (ref "R27") (pin "1") (pinfunction "1_1") (pintype "passive"))
    )
    (net (code "105") (name "/LED1") (class "Default")
      (node (ref "R28") (pin "1") (pinfunction "1_1") (pintype "passive"))
    )
    (net (code "106") (name "/LED2") (class "Default")
      (node (ref "R29") (pin "1") (pinfunction "1_1") (pintype "passive"))
    )
    (net (code "107") (name "/LED3") (class "Default")
      (node (ref "R30") (pin "1") (pinfunction "1_1") (pintype "passive"))
    )
    (net (code "108") (name "/LED4") (class "Default")
      (node (ref "R43") (pin "1") (pinfunction "1_1") (pintype "passive"))
    )
    (net (code "109") (name "/LED5") (class "Default")
      (node (ref "R44") (pin "1") (pinfunction "1_1") (pintype "passive"))
    )
    (net (code "110") (name "/LED6") (class "Default")
      (node (ref "R25") (pin "1") (pinfunction "1_1") (pintype "passive"))
    )
    (net (code "111") (name "/LED7") (class "Default")
      (node (ref "R26") (pin "1") (pinfunction "1_1") (pintype "passive"))
    )
    (net (code "114") (name "/LVDS0_N_1") (class "Default")
      (node (ref "IC4") (pin "5") (pinfunction "DOUT-_5") (pintype "output"))
    )
    (net (code "116") (name "/LVDS0_P_1") (class "Default")
      (node (ref "IC4") (pin "6") (pinfunction "DOUT+_6") (pintype "output"))
    )
    (net (code "118") (name "/LVDS1_N_1") (class "Default")
      (node (ref "IC16") (pin "5") (pinfunction "DOUT-_5") (pintype "output"))
    )
    (net (code "120") (name "/LVDS1_P_1") (class "Default")
      (node (ref "IC16") (pin "6") (pinfunction "DOUT+_6") (pintype "output"))
    )
    (net (code "121") (name "/LVDS7_N") (class "Default")
      (node (ref "IC9") (pin "11") (pinfunction "~{CLK0}_11") (pintype "input"))
    )
    (net (code "123") (name "/LVDS7_P") (class "Default")
      (node (ref "IC9") (pin "10") (pinfunction "CLK0_10") (pintype "input"))
    )
    (net (code "129") (name "/RF_OUT0") (class "Default")
      (node (ref "J3") (pin "1") (pinfunction "1_1") (pintype "bidirectional"))
    )
    (net (code "130") (name "/RF_OUT1") (class "Default")
      (node (ref "J4") (pin "1") (pinfunction "1_1") (pintype "bidirectional"))
    )
    (net (code "131") (name "/RF_OUT2") (class "Default")
      (node (ref "J5") (pin "1") (pinfunction "1_1") (pintype "bidirectional"))
    )
    (net (code "132") (name "/RF_OUT3") (class "Default")
      (node (ref "J6") (pin "1") (pinfunction "1_1") (pintype "bidirectional"))
    )
    (net (code "135") (name "/SG0") (class "Default")
      (node (ref "C37") (pin "1") (pinfunction "1_1") (pintype "passive"))
      (node (ref "C42") (pin "2") (pinfunction "2_2") (pintype "passive"))
      (node (ref "J2") (pin "2") (pinfunction "2_2") (pintype "bidirectional"))
      (node (ref "R6") (pin "2") (pinfunction "2_2") (pintype "passive"))
    )
    (net (code "136") (name "/SG1") (class "Default")
      (node (ref "C11") (pin "1") (pinfunction "1_1") (pintype "passive"))
      (node (ref "C25") (pin "2") (pinfunction "2_2") (pintype "passive"))
      (node (ref "J3") (pin "2") (pinfunction "2_2") (pintype "bidirectional"))
      (node (ref "R64") (pin "2") (pinfunction "2_2") (pintype "passive"))
    )
    (net (code "137") (name "/SG2") (class "Default")
      (node (ref "C31") (pin "1") (pinfunction "1_1") (pintype "passive"))
      (node (ref "C32") (pin "2") (pinfunction "2_2") (pintype "passive"))
      (node (ref "J4") (pin "2") (pinfunction "2_2") (pintype "bidirectional"))
      (node (ref "R65") (pin "2") (pinfunction "2_2") (pintype "passive"))
    )
    (net (code "138") (name "/SG3") (class "Default")
      (node (ref "C33") (pin "1") (pinfunction "1_1") (pintype "passive"))
      (node (ref "C34") (pin "2") (pinfunction "2_2") (pintype "passive"))
      (node (ref "J5") (pin "2") (pinfunction "2_2") (pintype "bidirectional"))
      (node (ref "R74") (pin "2") (pinfunction "2_2") (pintype "passive"))
    )
    (net (code "139") (name "/SG4") (class "Default")
      (node (ref "C35") (pin "1") (pinfunction "1_1") (pintype "passive"))
      (node (ref "C41") (pin "2") (pinfunction "2_2") (pintype "passive"))
      (node (ref "J6") (pin "2") (pinfunction "2_2") (pintype "bidirectional"))
      (node (ref "R75") (pin "2") (pinfunction "2_2") (pintype "passive"))
    )
    (net (code "172") (name "GND") (class "Default")
      (node (ref "C1") (pin "1") (pinfunction "1_1") (pintype "passive"))
      (node (ref "C11") (pin "2") (pinfunction "2_2") (pintype "passive"))
      (node (ref "C13") (pin "1") (pinfunction "1_1") (pintype "passive"))
      (node (ref "C25") (pin "1") (pinfunction "1_1") (pintype "passive"))
      (node (ref "C31") (pin "2") (pinfunction "2_2") (pintype "passive"))
      (node (ref "C32") (pin "1") (pinfunction "1_1") (pintype "passive"))
      (node (ref "C33") (pin "2") (pinfunction "2_2") (pintype "passive"))
      (node (ref "C34") (pin "1") (pinfunction "1_1") (pintype "passive"))
      (node (ref "C35") (pin "2") (pinfunction "2_2") (pintype "passive"))
      (node (ref "C37") (pin "2") (pinfunction "2_2") (pintype "passive"))
      (node (ref "C41") (pin "1") (pinfunction "1_1") (pintype "passive"))
      (node (ref "C42") (pin "1") (pinfunction "1_1") (pintype "passive"))
      (node (ref "C45") (pin "1") (pinfunction "1_1") (pintype "passive"))
      (node (ref "C46") (pin "1") (pinfunction "1_1") (pintype "passive"))
      (node (ref "C86") (pin "1") (pinfunction "1_1") (pintype "passive"))
      (node (ref "C89") (pin "1") (pinfunction "1_1") (pintype "passive"))
      (node (ref "C90") (pin "1") (pinfunction "1_1") (pintype "passive"))
      (node (ref "CLIP1") (pin "1") (pinfunction "1_1") (pintype "passive"))
      (node (ref "CLIP10") (pin "1") (pinfunction "1_1") (pintype "passive"))
      (node (ref "CLIP11") (pin "1") (pinfunction "1_1") (pintype "passive"))
      (node (ref "CLIP12") (pin "1") (pinfunction "1_1") (pintype "passive"))
      (node (ref "CLIP13") (pin "1") (pinfunction "1_1") (pintype "passive"))
      (node (ref "CLIP14") (pin "1") (pinfunction "1_1") (pintype "passive"))
      (node (ref "CLIP15") (pin "1") (pinfunction "1_1") (pintype "passive"))
      (node (ref "CLIP16") (pin "1") (pinfunction "1_1") (pintype "passive"))
      (node (ref "CLIP17") (pin "1") (pinfunction "1_1") (pintype "passive"))
      (node (ref "CLIP18") (pin "1") (pinfunction "1_1") (pintype "passive"))
      (node (ref "CLIP19") (pin "1") (pinfunction "1_1") (pintype "passive"))
      (node (ref "CLIP2") (pin "1") (pinfunction "1_1") (pintype "passive"))
      (node (ref "CLIP20") (pin "1") (pinfunction "1_1") (pintype "passive"))
      (node (ref "CLIP21") (pin "1") (pinfunction "1_1") (pintype "passive"))
      (node (ref "CLIP22") (pin "1") (pinfunction "1_1") (pintype "passive"))
      (node (ref "CLIP23") (pin "1") (pinfunction "1_1") (pintype "passive"))
      (node (ref "CLIP24") (pin "1") (pinfunction "1_1") (pintype "passive"))
      (node (ref "CLIP25") (pin "1") (pinfunction "1_1") (pintype "passive"))
      (node (ref "CLIP26") (pin "1") (pinfunction "1_1") (pintype "passive"))
      (node (ref "CLIP27") (pin "1") (pinfunction "1_1") (pintype "passive"))
      (node (ref "CLIP28") (pin "1") (pinfunction "1_1") (pintype "passive"))
      (node (ref "CLIP29") (pin "1") (pinfunction "1_1") (pintype "passive"))
      (node (ref "CLIP3") (pin "1") (pinfunction "1_1") (pintype "passive"))
      (node (ref "CLIP30") (pin "1") (pinfunction "1_1") (pintype "passive"))
      (node (ref "CLIP31") (pin "1") (pinfunction "1_1") (pintype "passive"))
      (node (ref "CLIP4") (pin "1") (pinfunction "1_1") (pintype "passive"))
      (node (ref "CLIP5") (pin "1") (pinfunction "1_1") (pintype "passive"))
      (node (ref "CLIP6") (pin "1") (pinfunction "1_1") (pintype "passive"))
      (node (ref "CLIP7") (pin "1") (pinfunction "1_1") (pintype "passive"))
      (node (ref "CLIP8") (pin "1") (pinfunction "1_1") (pintype "passive"))
      (node (ref "CLIP9") (pin "1") (pinfunction "1_1") (pintype "passive"))
      (node (ref "IC16") (pin "2") (pinfunction "GND_2") (pintype "power_in"))
      (node (ref "IC16") (pin "4") (pinfunction "GND_4") (pintype "output"))
      (node (ref "IC4") (pin "2") (pinfunction "GND_2") (pintype "power_in"))
      (node (ref "IC4") (pin "4") (pinfunction "GND_4") (pintype "output"))
      (node (ref "IC9") (pin "12") (pinfunction "OE2_12") (pintype "input"))
      (node (ref "IC9") (pin "2") (pinfunction "SFOUTA1_2") (pintype "input"))
      (node (ref "IC9") (pin "22") (pinfunction "SFOUTB0_22") (pintype "input"))
      (node (ref "IC9") (pin "23") (pinfunction "SFOUTB1_23") (pintype "input"))
      (node (ref "IC9") (pin "3") (pinfunction "SFOUTA0_3") (pintype "input"))
      (node (ref "IC9") (pin "33") (pinfunction "GND_33") (pintype "power_in"))
      (node (ref "IC9") (pin "6") (pinfunction "GND_6") (pintype "power_in"))
      (node (ref "J7") (pin "2") (pinfunction "2_2") (pintype "bidirectional"))
      (node (ref "LD2") (pin "1") (pinfunction "C_1") (pintype "passive"))
      (node (ref "LD2") (pin "3") (pinfunction "C_3") (pintype "passive"))
      (node (ref "LD5") (pin "1") (pinfunction "C_1") (pintype "passive"))
      (node (ref "LD5") (pin "3") (pinfunction "C_3") (pintype "passive"))
      (node (ref "LD6") (pin "1") (pinfunction "C_1") (pintype "passive"))
      (node (ref "LD6") (pin "3") (pinfunction "C_3") (pintype "passive"))
      (node (ref "LD8") (pin "1") (pinfunction "C_1") (pintype "passive"))
      (node (ref "LD8") (pin "3") (pinfunction "C_3") (pintype "passive"))
      (node (ref "R39") (pin "1") (pinfunction "1_1") (pintype "passive"))
      (node (ref "R6") (pin "1") (pinfunction "1_1") (pintype "passive"))
      (node (ref "R64") (pin "1") (pinfunction "1_1") (pintype "passive"))
      (node (ref "R65") (pin "1") (pinfunction "1_1") (pintype "passive"))
      (node (ref "R74") (pin "1") (pinfunction "1_1") (pintype "passive"))
      (node (ref "R75") (pin "1") (pinfunction "1_1") (pintype "passive"))
    )
    (net (code "173") (name "Net-(IC4-RIN+)") (class "Default")
      (node (ref "IC4") (pin "8") (pinfunction "RIN+_8") (pintype "input"))
      (node (ref "R31") (pin "1") (pinfunction "1_1") (pintype "passive"))
      (node (ref "R32") (pin "2") (pinfunction "2_2") (pintype "passive"))
    )
    (net (code "174") (name "Net-(IC4-RIN-)") (class "Default")
      (node (ref "C1") (pin "2") (pinfunction "2_2") (pintype "passive"))
      (node (ref "IC4") (pin "1") (pinfunction "RIN-_1") (pintype "input"))
      (node (ref "R32") (pin "1") (pinfunction "1_1") (pintype "passive"))
      (node (ref "R36") (pin "1") (pinfunction "1_1") (pintype "passive"))
      (node (ref "R39") (pin "2") (pinfunction "2_2") (pintype "passive"))
    )
    (net (code "175") (name "Net-(LD2A-A)") (class "Default")
      (node (ref "LD2") (pin "2") (pinfunction "A_2") (pintype "passive"))
      (node (ref "R25") (pin "2") (pinfunction "2_2") (pintype "passive"))
    )
    (net (code "176") (name "Net-(LD2B-A)") (class "Default")
      (node (ref "LD2") (pin "4") (pinfunction "A_4") (pintype "passive"))
      (node (ref "R26") (pin "2") (pinfunction "2_2") (pintype "passive"))
    )
    (net (code "177") (name "Net-(LD5A-A)") (class "Default")
      (node (ref "LD5") (pin "2") (pinfunction "A_2") (pintype "passive"))
      (node (ref "R27") (pin "2") (pinfunction "2_2") (pintype "passive"))
    )
    (net (code "178") (name "Net-(LD5B-A)") (class "Default")
      (node (ref "LD5") (pin "4") (pinfunction "A_4") (pintype "passive"))
      (node (ref "R28") (pin "2") (pinfunction "2_2") (pintype "passive"))
    )
    (net (code "179") (name "Net-(LD6A-A)") (class "Default")
      (node (ref "LD6") (pin "2") (pinfunction "A_2") (pintype "passive"))
      (node (ref "R29") (pin "2") (pinfunction "2_2") (pintype "passive"))
    )
    (net (code "180") (name "Net-(LD6B-A)") (class "Default")
      (node (ref "LD6") (pin "4") (pinfunction "A_4") (pintype "passive"))
      (node (ref "R30") (pin "2") (pinfunction "2_2") (pintype "passive"))
    )
    (net (code "181") (name "Net-(LD8A-A)") (class "Default")
      (node (ref "LD8") (pin "2") (pinfunction "A_2") (pintype "passive"))
      (node (ref "R43") (pin "2") (pinfunction "2_2") (pintype "passive"))
    )
    (net (code "182") (name "Net-(LD8B-A)") (class "Default")
      (node (ref "LD8") (pin "4") (pinfunction "A_4") (pintype "passive"))
      (node (ref "R44") (pin "2") (pinfunction "2_2") (pintype "passive"))
    )
    (net (code "183") (name "P3V3") (class "Default")
      (node (ref "L13") (pin "2") (pinfunction "2_2") (pintype "passive"))
      (node (ref "L8") (pin "2") (pinfunction "2_2") (pintype "passive"))
    )
    (net (code "184") (name "P3V3_CLK1") (class "Default")
      (node (ref "C86") (pin "2") (pinfunction "2_2") (pintype "passive"))
      (node (ref "C89") (pin "2") (pinfunction "2_2") (pintype "passive"))
      (node (ref "C90") (pin "2") (pinfunction "2_2") (pintype "passive"))
      (node (ref "IC9") (pin "1") (pinfunction "OE0_1") (pintype "input"))
      (node (ref "IC9") (pin "13") (pinfunction "OE3_13") (pintype "input"))
      (node (ref "IC9") (pin "16") (pinfunction "OE4_16") (pintype "input"))
      (node (ref "IC9") (pin "18") (pinfunction "VDDOA_18") (pintype "power_in"))
      (node (ref "IC9") (pin "19") (pinfunction "VDDOB_19") (pintype "power_in"))
      (node (ref "IC9") (pin "24") (pinfunction "OE5_24") (pintype "input"))
      (node (ref "IC9") (pin "7") (pinfunction "VDD_7") (pintype "power_in"))
      (node (ref "IC9") (pin "9") (pinfunction "OE1_9") (pintype "input"))
      (node (ref "L13") (pin "1") (pinfunction "1_1") (pintype "passive"))
    )
    (net (code "185") (name "P3V3_CLK2") (class "Default")
      (node (ref "C13") (pin "2") (pinfunction "2_2") (pintype "passive"))
      (node (ref "C45") (pin "2") (pinfunction "2_2") (pintype "passive"))
      (node (ref "C46") (pin "2") (pinfunction "2_2") (pintype "passive"))
      (node (ref "IC16") (pin "7") (pinfunction "VCC_7") (pintype "power_in"))
      (node (ref "IC4") (pin "7") (pinfunction "VCC_7") (pintype "power_in"))
      (node (ref "L8") (pin "1") (pinfunction "1_1") (pintype "passive"))
      (node (ref "R36") (pin "2") (pinfunction "2_2") (pintype "passive"))
    )
    (net (code "186") (name "unconnected-(IC9-Q2-Pad30)") (class "Default")
      (node (ref "IC9") (pin "30") (pinfunction "Q2_30") (pintype "output"))
    )
    (net (code "187") (name "unconnected-(IC9-VREF-Pad17)") (class "Default")
      (node (ref "IC9") (pin "17") (pinfunction "VREF_17") (pintype "output"))
    )
    (net (code "188") (name "unconnected-(IC9-~{Q2}-Pad29)") (class "Default")
      (node (ref "IC9") (pin "29") (pinfunction "~{Q2}_29") (pintype "output"))
    )
  )
)
